# vocore_badge.net
KiCad netlist of a schematic drawn in EAGLE
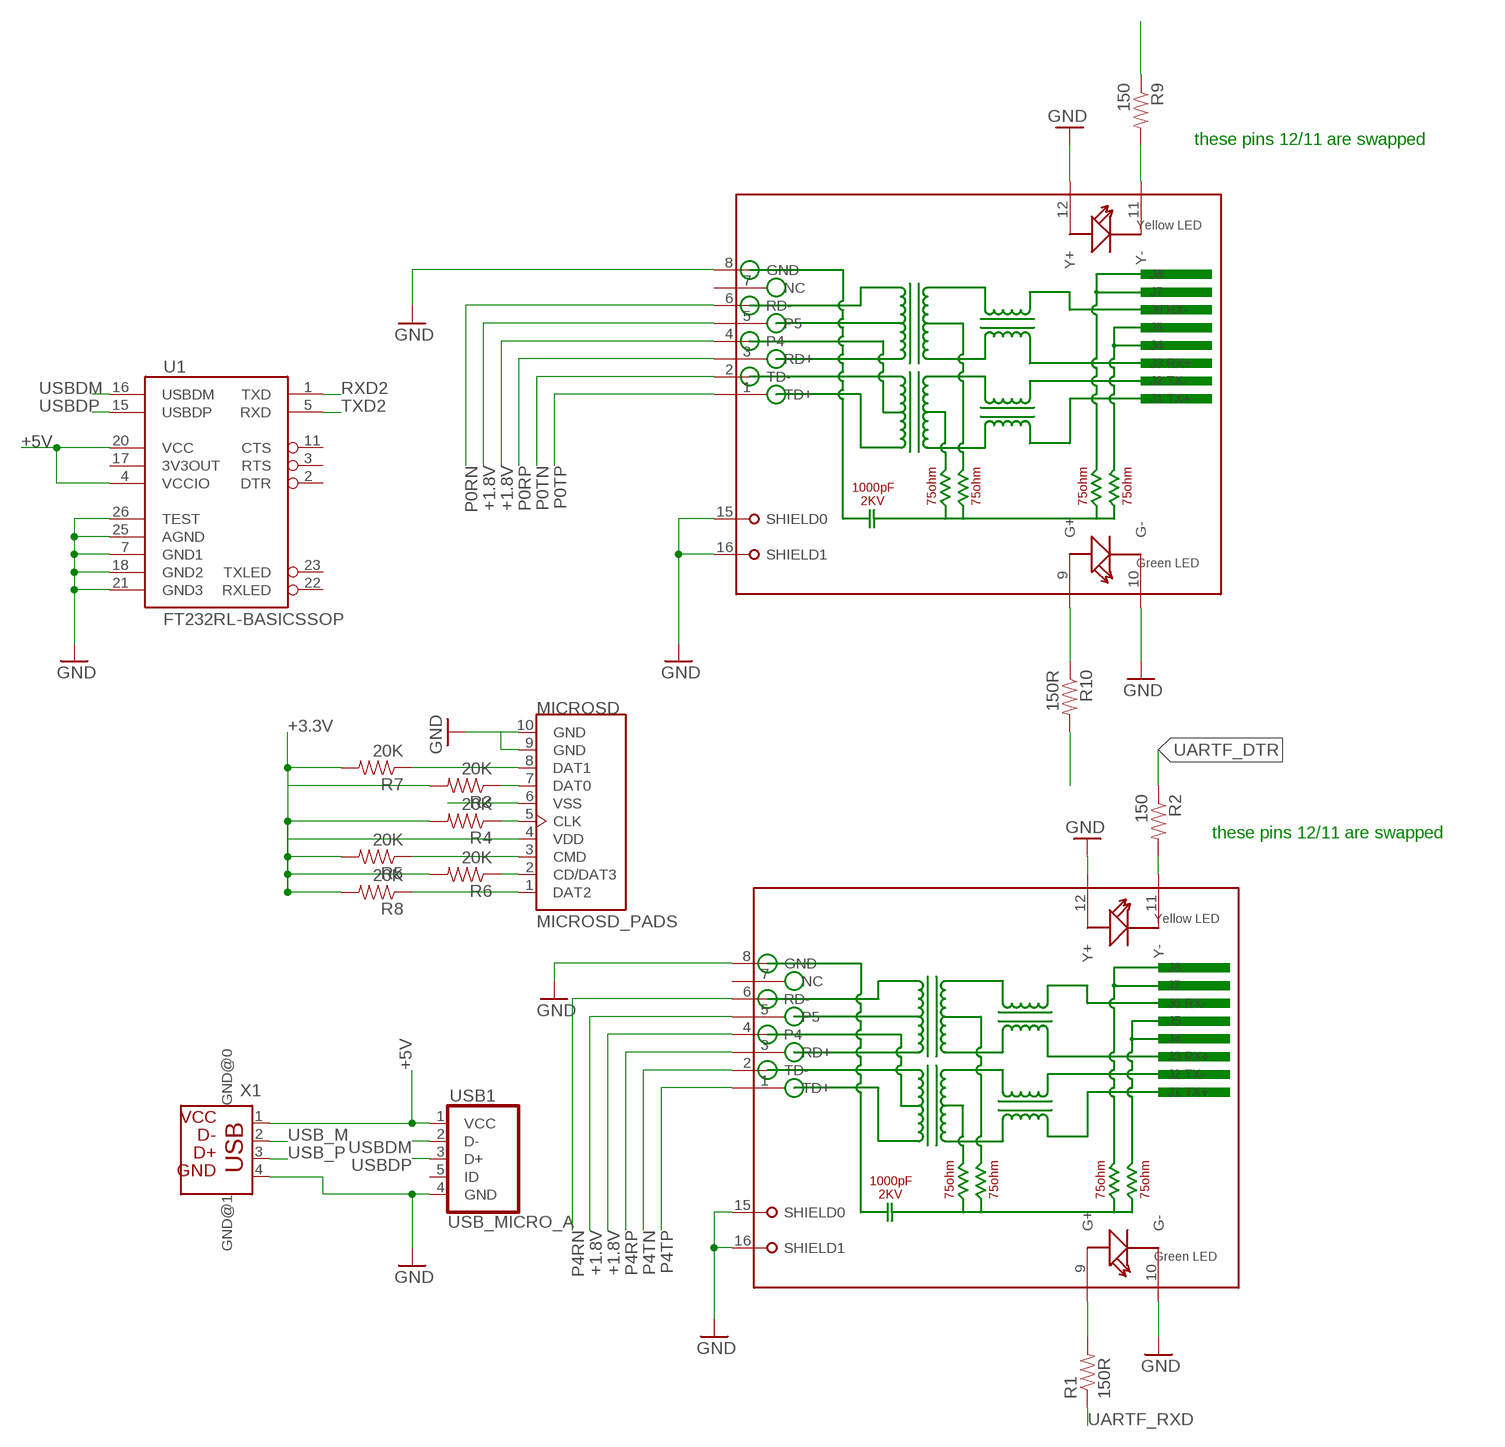
[diagram p0: schematic, sheet 1]
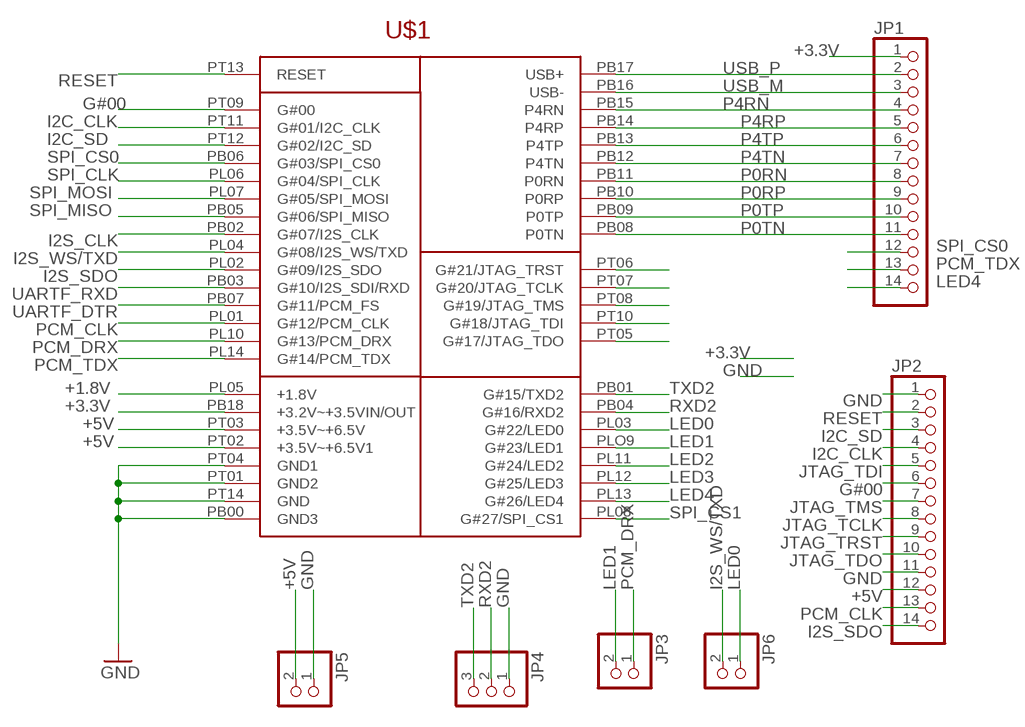
[diagram p1: schematic, sheet 2]

(export (version "E")
  (design (tool "Eeschema 10.0.6"))
  (components
    (comp (ref "MICROSD")
      (value "MICROSD_PADS")
      (footprint "eagle-import:MICROSD_PADS_1PRIMARY")
      (libsource (lib "eagle-import") (part "MICROSD_PADS"))
    )
    (comp (ref "R1")
      (value "150R")
      (footprint "eagle-import:0805")
      (libsource (lib "eagle-import") (part "RESISTOR0805-RES"))
    )
    (comp (ref "R2")
      (value "150")
      (footprint "eagle-import:0805")
      (libsource (lib "eagle-import") (part "RESISTOR0805-RES"))
    )
    (comp (ref "R3")
      (value "20K")
      (footprint "eagle-import:0805")
      (libsource (lib "eagle-import") (part "RESISTOR0805-RES"))
    )
    (comp (ref "R4")
      (value "20K")
      (footprint "eagle-import:0805")
      (libsource (lib "eagle-import") (part "RESISTOR0805-RES"))
    )
    (comp (ref "R5")
      (value "20K")
      (footprint "eagle-import:0805")
      (libsource (lib "eagle-import") (part "RESISTOR0805-RES"))
    )
    (comp (ref "R6")
      (value "20K")
      (footprint "eagle-import:0805")
      (libsource (lib "eagle-import") (part "RESISTOR0805-RES"))
    )
    (comp (ref "R7")
      (value "20K")
      (footprint "eagle-import:0805")
      (libsource (lib "eagle-import") (part "RESISTOR0805-RES"))
    )
    (comp (ref "R8")
      (value "20K")
      (footprint "eagle-import:0805")
      (libsource (lib "eagle-import") (part "RESISTOR0805-RES"))
    )
    (comp (ref "R9")
      (value "150")
      (footprint "eagle-import:0805")
      (libsource (lib "eagle-import") (part "RESISTOR0805-RES"))
    )
    (comp (ref "R10")
      (value "150R")
      (footprint "eagle-import:0805")
      (libsource (lib "eagle-import") (part "RESISTOR0805-RES"))
    )
    (comp (ref "RJ1")
      (value "RJ45ALED")
      (footprint "eagle-import:RJ45ALED_1PRIMARY")
      (libsource (lib "eagle-import") (part "HR911105AHR911105A"))
    )
    (comp (ref "RJ45")
      (value "RJ45ALED")
      (footprint "eagle-import:RJ45ALED_1PRIMARY")
      (libsource (lib "eagle-import") (part "HR911105AHR911105A"))
    )
    (comp (ref "U1")
      (value "FT232RL-BASICSSOP")
      (footprint "eagle-import:SSOP28DB")
      (libsource (lib "eagle-import") (part "FT232RL-BASICSSOP"))
    )
    (comp (ref "USB1")
      (value "USB_MICRO_A")
      (footprint "eagle-import:USB_MICRO_A_1PRIMARY")
      (libsource (lib "eagle-import") (part "USB_MICRO_AUSB_MICRO_A"))
    )
    (comp (ref "X1")
      (value "USB-787616")
      (footprint "eagle-import:USB")
      (libsource (lib "eagle-import") (part "USB-787616"))
    )
    (comp (ref "JP1")
      (value "PINHD-1X14")
      (footprint "eagle-import:1X14")
      (libsource (lib "eagle-import") (part "PINHD-1X14"))
    )
    (comp (ref "JP2")
      (value "PINHD-1X14")
      (footprint "eagle-import:1X14")
      (libsource (lib "eagle-import") (part "PINHD-1X14"))
    )
    (comp (ref "JP3")
      (value "PINHD-1X2")
      (footprint "eagle-import:1X02")
      (libsource (lib "eagle-import") (part "PINHD-1X2"))
    )
    (comp (ref "JP4")
      (value "PINHD-1X3")
      (footprint "eagle-import:1X03")
      (libsource (lib "eagle-import") (part "PINHD-1X3"))
    )
    (comp (ref "JP5")
      (value "PINHD-1X2")
      (footprint "eagle-import:1X02")
      (libsource (lib "eagle-import") (part "PINHD-1X2"))
    )
    (comp (ref "JP6")
      (value "PINHD-1X2")
      (footprint "eagle-import:1X02")
      (libsource (lib "eagle-import") (part "PINHD-1X2"))
    )
    (comp (ref "U$1")
      (value "VOCORE_SHIELD")
      (footprint "eagle-import:VOCORE_DOC_CUSTOM")
      (libsource (lib "eagle-import") (part "VOCORE_SHIELD"))
    )
  )
  (nets
    (net (code "1") (name "+1.8V") (class "Default")
      (node (ref "RJ1") (pin "4") (pinfunction "P4_4") (pintype "bidirectional"))
      (node (ref "RJ1") (pin "5") (pinfunction "P5_5") (pintype "bidirectional"))
      (node (ref "RJ45") (pin "4") (pinfunction "P4_4") (pintype "bidirectional"))
      (node (ref "RJ45") (pin "5") (pinfunction "P5_5") (pintype "bidirectional"))
      (node (ref "U$1") (pin "PL05") (pinfunction "+1.8V_PL05") (pintype "bidirectional"))
    )
    (net (code "2") (name "+3.3V") (class "Default")
      (node (ref "JP1") (pin "1") (pinfunction "1_1") (pintype "passive"))
      (node (ref "MICROSD") (pin "4") (pinfunction "VDD_4") (pintype "bidirectional"))
      (node (ref "R3") (pin "2") (pinfunction "2_2") (pintype "passive"))
      (node (ref "R4") (pin "2") (pinfunction "2_2") (pintype "passive"))
      (node (ref "R5") (pin "2") (pinfunction "2_2") (pintype "passive"))
      (node (ref "R6") (pin "2") (pinfunction "2_2") (pintype "passive"))
      (node (ref "R7") (pin "2") (pinfunction "2_2") (pintype "passive"))
      (node (ref "R8") (pin "2") (pinfunction "2_2") (pintype "passive"))
      (node (ref "U$1") (pin "PB18") (pinfunction "+3.2V~{+3.5VIN/OUT}_PB18") (pintype "bidirectional"))
    )
    (net (code "3") (name "+5V") (class "Default")
      (node (ref "JP2") (pin "12") (pinfunction "12_12") (pintype "passive"))
      (node (ref "JP5") (pin "2") (pinfunction "2_2") (pintype "passive"))
      (node (ref "U$1") (pin "PT02") (pinfunction "+3.5V~{+6.5V1}_PT02") (pintype "bidirectional"))
      (node (ref "U$1") (pin "PT03") (pinfunction "+3.5V~{+6.5V}_PT03") (pintype "bidirectional"))
      (node (ref "U1") (pin "20") (pinfunction "VCC_20") (pintype "power_in"))
      (node (ref "U1") (pin "4") (pinfunction "VCCIO_4") (pintype "power_in"))
      (node (ref "USB1") (pin "1") (pinfunction "VCC_1") (pintype "bidirectional"))
      (node (ref "X1") (pin "1") (pinfunction "1_1") (pintype "passive"))
    )
    (net (code "4") (name "5") (class "Default")
      (node (ref "X1") (pin "GND@0") (pinfunction "5_GND@0") (pintype "power_in"))
    )
    (net (code "5") (name "6") (class "Default")
      (node (ref "X1") (pin "GND@1") (pinfunction "6_GND@1") (pintype "power_in"))
    )
    (net (code "6") (name "G#00") (class "Default")
      (node (ref "JP2") (pin "6") (pinfunction "6_6") (pintype "passive"))
      (node (ref "U$1") (pin "PT09") (pinfunction "G#00_PT09") (pintype "bidirectional"))
    )
    (net (code "7") (name "GND") (class "Default")
      (node (ref "JP2") (pin "1") (pinfunction "1_1") (pintype "passive"))
      (node (ref "JP2") (pin "11") (pinfunction "11_11") (pintype "passive"))
      (node (ref "JP4") (pin "1") (pinfunction "1_1") (pintype "passive"))
      (node (ref "JP5") (pin "1") (pinfunction "1_1") (pintype "passive"))
      (node (ref "MICROSD") (pin "10") (pinfunction "GND_10") (pintype "power_in"))
      (node (ref "MICROSD") (pin "6") (pinfunction "VSS_6") (pintype "power_in"))
      (node (ref "MICROSD") (pin "9") (pinfunction "GND_9") (pintype "power_in"))
      (node (ref "RJ1") (pin "10") (pinfunction "G-_10") (pintype "bidirectional"))
      (node (ref "RJ1") (pin "12") (pinfunction "Y+_12") (pintype "bidirectional"))
      (node (ref "RJ1") (pin "15") (pinfunction "SHIELD0_15") (pintype "bidirectional"))
      (node (ref "RJ1") (pin "16") (pinfunction "SHIELD1_16") (pintype "bidirectional"))
      (node (ref "RJ1") (pin "8") (pinfunction "GND_8") (pintype "bidirectional"))
      (node (ref "RJ45") (pin "10") (pinfunction "G-_10") (pintype "bidirectional"))
      (node (ref "RJ45") (pin "12") (pinfunction "Y+_12") (pintype "bidirectional"))
      (node (ref "RJ45") (pin "15") (pinfunction "SHIELD0_15") (pintype "bidirectional"))
      (node (ref "RJ45") (pin "16") (pinfunction "SHIELD1_16") (pintype "bidirectional"))
      (node (ref "RJ45") (pin "8") (pinfunction "GND_8") (pintype "bidirectional"))
      (node (ref "U$1") (pin "PB00") (pinfunction "GND3_PB00") (pintype "bidirectional"))
      (node (ref "U$1") (pin "PT01") (pinfunction "GND2_PT01") (pintype "bidirectional"))
      (node (ref "U$1") (pin "PT04") (pinfunction "GND1_PT04") (pintype "bidirectional"))
      (node (ref "U$1") (pin "PT14") (pinfunction "GND_PT14") (pintype "bidirectional"))
      (node (ref "U1") (pin "18") (pinfunction "GND2_18") (pintype "power_in"))
      (node (ref "U1") (pin "21") (pinfunction "GND3_21") (pintype "power_in"))
      (node (ref "U1") (pin "25") (pinfunction "AGND_25") (pintype "power_in"))
      (node (ref "U1") (pin "26") (pinfunction "TEST_26") (pintype "input"))
      (node (ref "U1") (pin "7") (pinfunction "GND1_7") (pintype "power_in"))
      (node (ref "USB1") (pin "4") (pinfunction "GND_4") (pintype "bidirectional"))
      (node (ref "X1") (pin "4") (pinfunction "4_4") (pintype "passive"))
    )
    (net (code "8") (name "I2C_CLK") (class "Default")
      (node (ref "JP2") (pin "4") (pinfunction "4_4") (pintype "passive"))
      (node (ref "U$1") (pin "PT11") (pinfunction "G#01/I2C_CLK_PT11") (pintype "bidirectional"))
    )
    (net (code "9") (name "I2C_SD") (class "Default")
      (node (ref "JP2") (pin "3") (pinfunction "3_3") (pintype "passive"))
      (node (ref "U$1") (pin "PT12") (pinfunction "G#02/I2C_SD_PT12") (pintype "bidirectional"))
    )
    (net (code "10") (name "I2S_CLK") (class "Default")
      (node (ref "U$1") (pin "PB02") (pinfunction "G#07/I2S_CLK_PB02") (pintype "bidirectional"))
    )
    (net (code "11") (name "I2S_SDO") (class "Default")
      (node (ref "JP2") (pin "14") (pinfunction "14_14") (pintype "passive"))
      (node (ref "U$1") (pin "PL02") (pinfunction "G#09/I2S_SDO_PL02") (pintype "bidirectional"))
    )
    (net (code "12") (name "I2S_WS{slash}TXD") (class "Default")
      (node (ref "JP6") (pin "2") (pinfunction "2_2") (pintype "passive"))
      (node (ref "U$1") (pin "PL04") (pinfunction "G#08/I2S_WS/TXD_PL04") (pintype "bidirectional"))
    )
    (net (code "13") (name "JTAG_TCLK") (class "Default")
      (node (ref "JP2") (pin "8") (pinfunction "8_8") (pintype "passive"))
      (node (ref "U$1") (pin "PT07") (pinfunction "G#20/JTAG_TCLK_PT07") (pintype "bidirectional"))
    )
    (net (code "14") (name "JTAG_TDI") (class "Default")
      (node (ref "JP2") (pin "5") (pinfunction "5_5") (pintype "passive"))
      (node (ref "U$1") (pin "PT10") (pinfunction "G#18/JTAG_TDI_PT10") (pintype "bidirectional"))
    )
    (net (code "15") (name "JTAG_TDO") (class "Default")
      (node (ref "JP2") (pin "10") (pinfunction "10_10") (pintype "passive"))
      (node (ref "U$1") (pin "PT05") (pinfunction "G#17/JTAG_TDO_PT05") (pintype "bidirectional"))
    )
    (net (code "16") (name "JTAG_TMS") (class "Default")
      (node (ref "JP2") (pin "7") (pinfunction "7_7") (pintype "passive"))
      (node (ref "U$1") (pin "PT08") (pinfunction "G#19/JTAG_TMS_PT08") (pintype "bidirectional"))
    )
    (net (code "17") (name "JTAG_TRST") (class "Default")
      (node (ref "JP2") (pin "9") (pinfunction "9_9") (pintype "passive"))
      (node (ref "U$1") (pin "PT06") (pinfunction "G#21/JTAG_TRST_PT06") (pintype "bidirectional"))
    )
    (net (code "18") (name "LED0") (class "Default")
      (node (ref "JP6") (pin "1") (pinfunction "1_1") (pintype "passive"))
      (node (ref "U$1") (pin "PL03") (pinfunction "G#22/LED0_PL03") (pintype "bidirectional"))
    )
    (net (code "19") (name "LED1") (class "Default")
      (node (ref "JP3") (pin "2") (pinfunction "2_2") (pintype "passive"))
      (node (ref "U$1") (pin "PLO9") (pinfunction "G#23/LED1_PLO9") (pintype "bidirectional"))
    )
    (net (code "20") (name "LED2") (class "Default")
      (node (ref "R10") (pin "2") (pinfunction "2_2") (pintype "passive"))
      (node (ref "U$1") (pin "PL11") (pinfunction "G#24/LED2_PL11") (pintype "bidirectional"))
    )
    (net (code "21") (name "LED3") (class "Default")
      (node (ref "R9") (pin "1") (pinfunction "1_1") (pintype "passive"))
      (node (ref "U$1") (pin "PL12") (pinfunction "G#25/LED3_PL12") (pintype "bidirectional"))
    )
    (net (code "22") (name "LED4") (class "Default")
      (node (ref "JP1") (pin "14") (pinfunction "14_14") (pintype "passive"))
      (node (ref "U$1") (pin "PL13") (pinfunction "G#26/LED4_PL13") (pintype "bidirectional"))
    )
    (net (code "23") (name "Net-(MICROSD-DAT1)") (class "Default")
      (node (ref "MICROSD") (pin "8") (pinfunction "DAT1_8") (pintype "bidirectional"))
      (node (ref "R7") (pin "1") (pinfunction "1_1") (pintype "passive"))
    )
    (net (code "24") (name "Net-(MICROSD-DAT2)") (class "Default")
      (node (ref "MICROSD") (pin "1") (pinfunction "DAT2_1") (pintype "bidirectional"))
      (node (ref "R8") (pin "1") (pinfunction "1_1") (pintype "passive"))
    )
    (net (code "25") (name "Net-(RJ1-G+)") (class "Default")
      (node (ref "R10") (pin "1") (pinfunction "1_1") (pintype "passive"))
      (node (ref "RJ1") (pin "9") (pinfunction "G+_9") (pintype "bidirectional"))
    )
    (net (code "26") (name "Net-(RJ1-Y-)") (class "Default")
      (node (ref "R9") (pin "2") (pinfunction "2_2") (pintype "passive"))
      (node (ref "RJ1") (pin "11") (pinfunction "Y-_11") (pintype "bidirectional"))
    )
    (net (code "27") (name "Net-(RJ45-G+)") (class "Default")
      (node (ref "R1") (pin "2") (pinfunction "2_2") (pintype "passive"))
      (node (ref "RJ45") (pin "9") (pinfunction "G+_9") (pintype "bidirectional"))
    )
    (net (code "28") (name "Net-(RJ45-Y-)") (class "Default")
      (node (ref "R2") (pin "2") (pinfunction "2_2") (pintype "passive"))
      (node (ref "RJ45") (pin "11") (pinfunction "Y-_11") (pintype "bidirectional"))
    )
    (net (code "29") (name "P0RN") (class "Default")
      (node (ref "JP1") (pin "8") (pinfunction "8_8") (pintype "passive"))
      (node (ref "RJ1") (pin "6") (pinfunction "RD-_6") (pintype "bidirectional"))
      (node (ref "U$1") (pin "PB11") (pinfunction "P0RN_PB11") (pintype "bidirectional"))
    )
    (net (code "30") (name "P0RP") (class "Default")
      (node (ref "JP1") (pin "9") (pinfunction "9_9") (pintype "passive"))
      (node (ref "RJ1") (pin "3") (pinfunction "RD+_3") (pintype "bidirectional"))
      (node (ref "U$1") (pin "PB10") (pinfunction "P0RP_PB10") (pintype "bidirectional"))
    )
    (net (code "31") (name "P0TN") (class "Default")
      (node (ref "JP1") (pin "11") (pinfunction "11_11") (pintype "passive"))
      (node (ref "RJ1") (pin "2") (pinfunction "TD-_2") (pintype "bidirectional"))
      (node (ref "U$1") (pin "PB08") (pinfunction "P0TN_PB08") (pintype "bidirectional"))
    )
    (net (code "32") (name "P0TP") (class "Default")
      (node (ref "JP1") (pin "10") (pinfunction "10_10") (pintype "passive"))
      (node (ref "RJ1") (pin "1") (pinfunction "TD+_1") (pintype "bidirectional"))
      (node (ref "U$1") (pin "PB09") (pinfunction "P0TP_PB09") (pintype "bidirectional"))
    )
    (net (code "33") (name "P4RN") (class "Default")
      (node (ref "JP1") (pin "4") (pinfunction "4_4") (pintype "passive"))
      (node (ref "RJ45") (pin "6") (pinfunction "RD-_6") (pintype "bidirectional"))
      (node (ref "U$1") (pin "PB15") (pinfunction "P4RN_PB15") (pintype "bidirectional"))
    )
    (net (code "34") (name "P4RP") (class "Default")
      (node (ref "JP1") (pin "5") (pinfunction "5_5") (pintype "passive"))
      (node (ref "RJ45") (pin "3") (pinfunction "RD+_3") (pintype "bidirectional"))
      (node (ref "U$1") (pin "PB14") (pinfunction "P4RP_PB14") (pintype "bidirectional"))
    )
    (net (code "35") (name "P4TN") (class "Default")
      (node (ref "JP1") (pin "7") (pinfunction "7_7") (pintype "passive"))
      (node (ref "RJ45") (pin "2") (pinfunction "TD-_2") (pintype "bidirectional"))
      (node (ref "U$1") (pin "PB12") (pinfunction "P4TN_PB12") (pintype "bidirectional"))
    )
    (net (code "36") (name "P4TP") (class "Default")
      (node (ref "JP1") (pin "6") (pinfunction "6_6") (pintype "passive"))
      (node (ref "RJ45") (pin "1") (pinfunction "TD+_1") (pintype "bidirectional"))
      (node (ref "U$1") (pin "PB13") (pinfunction "P4TP_PB13") (pintype "bidirectional"))
    )
    (net (code "37") (name "PCM_CLK") (class "Default")
      (node (ref "JP2") (pin "13") (pinfunction "13_13") (pintype "passive"))
      (node (ref "U$1") (pin "PL01") (pinfunction "G#12/PCM_CLK_PL01") (pintype "bidirectional"))
    )
    (net (code "38") (name "PCM_DRX") (class "Default")
      (node (ref "JP3") (pin "1") (pinfunction "1_1") (pintype "passive"))
      (node (ref "U$1") (pin "PL10") (pinfunction "G#13/PCM_DRX_PL10") (pintype "bidirectional"))
    )
    (net (code "39") (name "PCM_TDX") (class "Default")
      (node (ref "JP1") (pin "13") (pinfunction "13_13") (pintype "passive"))
      (node (ref "U$1") (pin "PL14") (pinfunction "G#14/PCM_TDX_PL14") (pintype "bidirectional"))
    )
    (net (code "40") (name "RESET") (class "Default")
      (node (ref "JP2") (pin "2") (pinfunction "2_2") (pintype "passive"))
      (node (ref "U$1") (pin "PT13") (pinfunction "RESET_PT13") (pintype "bidirectional"))
    )
    (net (code "41") (name "RXD2") (class "Default")
      (node (ref "JP4") (pin "2") (pinfunction "2_2") (pintype "passive"))
      (node (ref "U$1") (pin "PB04") (pinfunction "G#16/RXD2_PB04") (pintype "bidirectional"))
      (node (ref "U1") (pin "1") (pinfunction "TXD_1") (pintype "output"))
    )
    (net (code "42") (name "SPI_CLK") (class "Default")
      (node (ref "MICROSD") (pin "5") (pinfunction "CLK_5") (pintype "bidirectional"))
      (node (ref "R4") (pin "1") (pinfunction "1_1") (pintype "passive"))
      (node (ref "U$1") (pin "PL06") (pinfunction "G#04/SPI_CLK_PL06") (pintype "bidirectional"))
    )
    (net (code "43") (name "SPI_CS0") (class "Default")
      (node (ref "JP1") (pin "12") (pinfunction "12_12") (pintype "passive"))
      (node (ref "U$1") (pin "PB06") (pinfunction "G#03/SPI_CS0_PB06") (pintype "bidirectional"))
    )
    (net (code "44") (name "SPI_CS1") (class "Default")
      (node (ref "MICROSD") (pin "2") (pinfunction "CD/DAT3_2") (pintype "bidirectional"))
      (node (ref "R6") (pin "1") (pinfunction "1_1") (pintype "passive"))
      (node (ref "U$1") (pin "PL08") (pinfunction "G#27/SPI_CS1_PL08") (pintype "bidirectional"))
    )
    (net (code "45") (name "SPI_MISO") (class "Default")
      (node (ref "MICROSD") (pin "7") (pinfunction "DAT0_7") (pintype "bidirectional"))
      (node (ref "R3") (pin "1") (pinfunction "1_1") (pintype "passive"))
      (node (ref "U$1") (pin "PB05") (pinfunction "G#06/SPI_MISO_PB05") (pintype "bidirectional"))
    )
    (net (code "46") (name "SPI_MOSI") (class "Default")
      (node (ref "MICROSD") (pin "3") (pinfunction "CMD_3") (pintype "bidirectional"))
      (node (ref "R5") (pin "1") (pinfunction "1_1") (pintype "passive"))
      (node (ref "U$1") (pin "PL07") (pinfunction "G#05/SPI_MOSI_PL07") (pintype "bidirectional"))
    )
    (net (code "47") (name "TXD2") (class "Default")
      (node (ref "JP4") (pin "3") (pinfunction "3_3") (pintype "passive"))
      (node (ref "U$1") (pin "PB01") (pinfunction "G#15/TXD2_PB01") (pintype "bidirectional"))
      (node (ref "U1") (pin "5") (pinfunction "RXD_5") (pintype "input"))
    )
    (net (code "48") (name "UARTF_DTR") (class "Default")
      (node (ref "R2") (pin "1") (pinfunction "1_1") (pintype "passive"))
      (node (ref "U$1") (pin "PB07") (pinfunction "G#11/PCM_FS_PB07") (pintype "bidirectional"))
    )
    (net (code "49") (name "UARTF_RXD") (class "Default")
      (node (ref "R1") (pin "1") (pinfunction "1_1") (pintype "passive"))
      (node (ref "U$1") (pin "PB03") (pinfunction "G#10/I2S_SDI/RXD_PB03") (pintype "bidirectional"))
    )
    (net (code "50") (name "USBDM") (class "Default")
      (node (ref "U1") (pin "16") (pinfunction "USBDM_16") (pintype "bidirectional"))
      (node (ref "USB1") (pin "2") (pinfunction "D-_2") (pintype "bidirectional"))
    )
    (net (code "51") (name "USBDP") (class "Default")
      (node (ref "U1") (pin "15") (pinfunction "USBDP_15") (pintype "bidirectional"))
      (node (ref "USB1") (pin "3") (pinfunction "D+_3") (pintype "bidirectional"))
    )
    (net (code "52") (name "USB_M") (class "Default")
      (node (ref "JP1") (pin "3") (pinfunction "3_3") (pintype "passive"))
      (node (ref "U$1") (pin "PB16") (pinfunction "USB-_PB16") (pintype "bidirectional"))
      (node (ref "X1") (pin "2") (pinfunction "2_2") (pintype "passive"))
    )
    (net (code "53") (name "USB_P") (class "Default")
      (node (ref "JP1") (pin "2") (pinfunction "2_2") (pintype "passive"))
      (node (ref "U$1") (pin "PB17") (pinfunction "USB+_PB17") (pintype "bidirectional"))
      (node (ref "X1") (pin "3") (pinfunction "3_3") (pintype "passive"))
    )
    (net (code "54") (name "unconnected-(RJ1-NC-Pad7)") (class "Default")
      (node (ref "RJ1") (pin "7") (pinfunction "NC_7") (pintype "bidirectional"))
    )
    (net (code "55") (name "unconnected-(RJ45-NC-Pad7)") (class "Default")
      (node (ref "RJ45") (pin "7") (pinfunction "NC_7") (pintype "bidirectional"))
    )
    (net (code "56") (name "unconnected-(U1-3V3OUT-Pad17)") (class "Default")
      (node (ref "U1") (pin "17") (pinfunction "3V3OUT_17") (pintype "output"))
    )
    (net (code "57") (name "unconnected-(U1-CTS-Pad11)") (class "Default")
      (node (ref "U1") (pin "11") (pinfunction "CTS_11") (pintype "bidirectional"))
    )
    (net (code "58") (name "unconnected-(U1-DTR-Pad2)") (class "Default")
      (node (ref "U1") (pin "2") (pinfunction "DTR_2") (pintype "bidirectional"))
    )
    (net (code "59") (name "unconnected-(U1-RTS-Pad3)") (class "Default")
      (node (ref "U1") (pin "3") (pinfunction "RTS_3") (pintype "bidirectional"))
    )
    (net (code "60") (name "unconnected-(U1-RXLED-Pad22)") (class "Default")
      (node (ref "U1") (pin "22") (pinfunction "RXLED_22") (pintype "bidirectional"))
    )
    (net (code "61") (name "unconnected-(U1-TXLED-Pad23)") (class "Default")
      (node (ref "U1") (pin "23") (pinfunction "TXLED_23") (pintype "bidirectional"))
    )
    (net (code "62") (name "unconnected-(USB1-ID-Pad5)") (class "Default")
      (node (ref "USB1") (pin "5") (pinfunction "ID_5") (pintype "bidirectional"))
    )
  )
)
